# v001.net
KiCad netlist of a schematic drawn in EAGLE
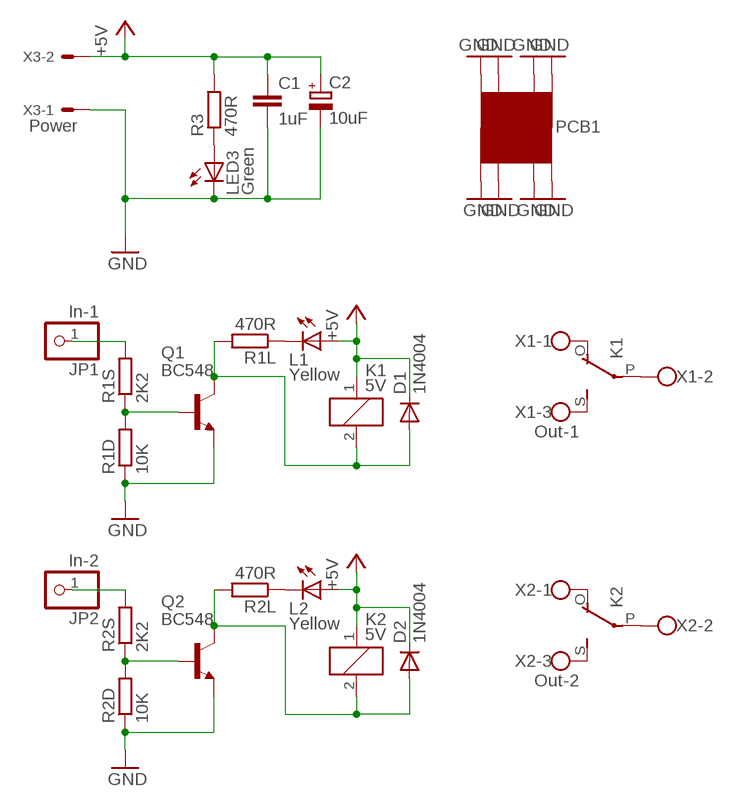
[diagram p0: schematic, sheet 1]

(export (version "E")
  (design (tool "Eeschema 10.0.6"))
  (components
    (comp (ref "C1")
      (value "1uF")
      (footprint "eagle-import:C050-035X075")
      (libsource (lib "eagle-import") (part "C-EU050-035X075"))
    )
    (comp (ref "C2")
      (value "10uF")
      (footprint "eagle-import:E2,5-5")
      (libsource (lib "eagle-import") (part "CPOL-EUE2.5-5"))
    )
    (comp (ref "D1")
      (value "1N4004")
      (footprint "eagle-import:DO41-10")
      (libsource (lib "eagle-import") (part "1N4004"))
    )
    (comp (ref "D2")
      (value "1N4004")
      (footprint "eagle-import:DO41-10")
      (libsource (lib "eagle-import") (part "1N4004"))
    )
    (comp (ref "JP1")
      (value "In-1")
      (footprint "eagle-import:1X01")
      (libsource (lib "eagle-import") (part "PINHD-1X1"))
    )
    (comp (ref "JP2")
      (value "In-2")
      (footprint "eagle-import:1X01")
      (libsource (lib "eagle-import") (part "PINHD-1X1"))
    )
    (comp (ref "K1")
      (value "5V")
      (footprint "eagle-import:G5LE")
      (libsource (lib "eagle-import") (part "G5L"))
    )
    (comp (ref "K2")
      (value "5V")
      (footprint "eagle-import:G5LE")
      (libsource (lib "eagle-import") (part "G5L"))
    )
    (comp (ref "L1")
      (value "Yellow")
      (footprint "eagle-import:LED3MM")
      (libsource (lib "eagle-import") (part "LED3MM"))
    )
    (comp (ref "L2")
      (value "Yellow")
      (footprint "eagle-import:LED3MM")
      (libsource (lib "eagle-import") (part "LED3MM"))
    )
    (comp (ref "LED3")
      (value "Green")
      (footprint "eagle-import:LED3MM")
      (libsource (lib "eagle-import") (part "LED3MM"))
    )
    (comp (ref "PCB1")
      (value "PCB05X05")
      (footprint "eagle-import:PCB_05X05")
      (libsource (lib "eagle-import") (part "PCB05X05"))
    )
    (comp (ref "Q1")
      (value "BC548")
      (footprint "eagle-import:TO92-EBC")
      (libsource (lib "eagle-import") (part "BC548"))
    )
    (comp (ref "Q2")
      (value "BC548")
      (footprint "eagle-import:TO92-EBC")
      (libsource (lib "eagle-import") (part "BC548"))
    )
    (comp (ref "R1D")
      (value "10K")
      (footprint "eagle-import:0204_7")
      (libsource (lib "eagle-import") (part "R-EU_0204/7"))
    )
    (comp (ref "R1L")
      (value "470R")
      (footprint "eagle-import:0204_7")
      (libsource (lib "eagle-import") (part "R-EU_0204/7"))
    )
    (comp (ref "R1S")
      (value "2K2")
      (footprint "eagle-import:0204_7")
      (libsource (lib "eagle-import") (part "R-EU_0204/7"))
    )
    (comp (ref "R2D")
      (value "10K")
      (footprint "eagle-import:0204_7")
      (libsource (lib "eagle-import") (part "R-EU_0204/7"))
    )
    (comp (ref "R2L")
      (value "470R")
      (footprint "eagle-import:0204_7")
      (libsource (lib "eagle-import") (part "R-EU_0204/7"))
    )
    (comp (ref "R2S")
      (value "2K2")
      (footprint "eagle-import:0204_7")
      (libsource (lib "eagle-import") (part "R-EU_0204/7"))
    )
    (comp (ref "R3")
      (value "470R")
      (footprint "eagle-import:0207_2V")
      (libsource (lib "eagle-import") (part "resistor_R-EU_0207/2V"))
    )
    (comp (ref "X1")
      (value "Out-1")
      (footprint "eagle-import:W237-103")
      (fields (field (name "MPN") "237-103"))
      (libsource (lib "eagle-import") (part "W237-103"))
    )
    (comp (ref "X2")
      (value "Out-2")
      (footprint "eagle-import:W237-103")
      (fields (field (name "MPN") "237-103"))
      (libsource (lib "eagle-import") (part "W237-103"))
    )
    (comp (ref "X3")
      (value "Power")
      (footprint "eagle-import:6410-02")
      (libsource (lib "eagle-import") (part "22-?-0227-2021"))
    )
  )
  (nets
    (net (code "1") (name "+5V") (class "Default")
      (node (ref "C1") (pin "1") (pinfunction "1_1") (pintype "passive"))
      (node (ref "C2") (pin "+") (pinfunction "+_+") (pintype "passive"))
      (node (ref "D1") (pin "C") (pinfunction "C_C") (pintype "passive"))
      (node (ref "D2") (pin "C") (pinfunction "C_C") (pintype "passive"))
      (node (ref "K1") (pin "1") (pinfunction "1_1") (pintype "passive"))
      (node (ref "K2") (pin "1") (pinfunction "1_1") (pintype "passive"))
      (node (ref "L1") (pin "A") (pinfunction "A_A") (pintype "passive"))
      (node (ref "L2") (pin "A") (pinfunction "A_A") (pintype "passive"))
      (node (ref "R3") (pin "2") (pinfunction "2_2") (pintype "passive"))
      (node (ref "X3") (pin "2") (pinfunction "S_2") (pintype "passive"))
    )
    (net (code "2") (name "GND") (class "Default")
      (node (ref "C1") (pin "2") (pinfunction "2_2") (pintype "passive"))
      (node (ref "C2") (pin "-") (pinfunction "-_-") (pintype "passive"))
      (node (ref "LED3") (pin "K") (pinfunction "C_K") (pintype "passive"))
      (node (ref "PCB1") (pin "GND@1") (pinfunction "GND_GND@1") (pintype "bidirectional"))
      (node (ref "PCB1") (pin "GND@2") (pinfunction "GND_GND@2") (pintype "bidirectional"))
      (node (ref "PCB1") (pin "GND@3") (pinfunction "GND_GND@3") (pintype "bidirectional"))
      (node (ref "PCB1") (pin "GND@4") (pinfunction "GND_GND@4") (pintype "bidirectional"))
      (node (ref "PCB1") (pin "GND@5") (pinfunction "GND_GND@5") (pintype "bidirectional"))
      (node (ref "PCB1") (pin "GND@6") (pinfunction "GND_GND@6") (pintype "bidirectional"))
      (node (ref "PCB1") (pin "GND@7") (pinfunction "GND_GND@7") (pintype "bidirectional"))
      (node (ref "PCB1") (pin "GND@8") (pinfunction "GND_GND@8") (pintype "bidirectional"))
      (node (ref "Q1") (pin "E") (pinfunction "E_E") (pintype "passive"))
      (node (ref "Q2") (pin "E") (pinfunction "E_E") (pintype "passive"))
      (node (ref "R1D") (pin "1") (pinfunction "1_1") (pintype "passive"))
      (node (ref "R2D") (pin "1") (pinfunction "1_1") (pintype "passive"))
      (node (ref "X3") (pin "1") (pinfunction "S_1") (pintype "passive"))
    )
    (net (code "3") (name "Net-(D1-PadA)") (class "Default")
      (node (ref "D1") (pin "A") (pinfunction "A_A") (pintype "passive"))
      (node (ref "K1") (pin "2") (pinfunction "2_2") (pintype "passive"))
      (node (ref "Q1") (pin "C") (pinfunction "C_C") (pintype "passive"))
      (node (ref "R1L") (pin "2") (pinfunction "2_2") (pintype "passive"))
    )
    (net (code "4") (name "Net-(D2-PadA)") (class "Default")
      (node (ref "D2") (pin "A") (pinfunction "A_A") (pintype "passive"))
      (node (ref "K2") (pin "2") (pinfunction "2_2") (pintype "passive"))
      (node (ref "Q2") (pin "C") (pinfunction "C_C") (pintype "passive"))
      (node (ref "R2L") (pin "2") (pinfunction "2_2") (pintype "passive"))
    )
    (net (code "5") (name "Net-(JP1-Pad1)") (class "Default")
      (node (ref "JP1") (pin "1") (pinfunction "1_1") (pintype "passive"))
      (node (ref "R1S") (pin "2") (pinfunction "2_2") (pintype "passive"))
    )
    (net (code "6") (name "Net-(JP2-Pad1)") (class "Default")
      (node (ref "JP2") (pin "1") (pinfunction "1_1") (pintype "passive"))
      (node (ref "R2S") (pin "2") (pinfunction "2_2") (pintype "passive"))
    )
    (net (code "7") (name "Net-(L1-C)") (class "Default")
      (node (ref "L1") (pin "K") (pinfunction "C_K") (pintype "passive"))
      (node (ref "R1L") (pin "1") (pinfunction "1_1") (pintype "passive"))
    )
    (net (code "8") (name "Net-(L2-C)") (class "Default")
      (node (ref "L2") (pin "K") (pinfunction "C_K") (pintype "passive"))
      (node (ref "R2L") (pin "1") (pinfunction "1_1") (pintype "passive"))
    )
    (net (code "9") (name "Net-(LED3-PadA)") (class "Default")
      (node (ref "LED3") (pin "A") (pinfunction "A_A") (pintype "passive"))
      (node (ref "R3") (pin "1") (pinfunction "1_1") (pintype "passive"))
    )
    (net (code "10") (name "Net-(Q1-PadB)") (class "Default")
      (node (ref "Q1") (pin "B") (pinfunction "B_B") (pintype "passive"))
      (node (ref "R1D") (pin "2") (pinfunction "2_2") (pintype "passive"))
      (node (ref "R1S") (pin "1") (pinfunction "1_1") (pintype "passive"))
    )
    (net (code "11") (name "Net-(Q2-PadB)") (class "Default")
      (node (ref "Q2") (pin "B") (pinfunction "B_B") (pintype "passive"))
      (node (ref "R2D") (pin "2") (pinfunction "2_2") (pintype "passive"))
      (node (ref "R2S") (pin "1") (pinfunction "1_1") (pintype "passive"))
    )
    (net (code "12") (name "Net-(X1A-KL)") (class "Default")
      (node (ref "K1") (pin "O") (pinfunction "O_O") (pintype "passive"))
      (node (ref "X1") (pin "1") (pinfunction "KL_1") (pintype "passive"))
    )
    (net (code "13") (name "Net-(X1B-KL)") (class "Default")
      (node (ref "K1") (pin "P") (pinfunction "P_P") (pintype "passive"))
      (node (ref "X1") (pin "2") (pinfunction "KL_2") (pintype "passive"))
    )
    (net (code "14") (name "Net-(X1C-KL)") (class "Default")
      (node (ref "K1") (pin "S") (pinfunction "S_S") (pintype "passive"))
      (node (ref "X1") (pin "3") (pinfunction "KL_3") (pintype "passive"))
    )
    (net (code "15") (name "Net-(X2A-KL)") (class "Default")
      (node (ref "K2") (pin "O") (pinfunction "O_O") (pintype "passive"))
      (node (ref "X2") (pin "1") (pinfunction "KL_1") (pintype "passive"))
    )
    (net (code "16") (name "Net-(X2B-KL)") (class "Default")
      (node (ref "K2") (pin "P") (pinfunction "P_P") (pintype "passive"))
      (node (ref "X2") (pin "2") (pinfunction "KL_2") (pintype "passive"))
    )
    (net (code "17") (name "Net-(X2C-KL)") (class "Default")
      (node (ref "K2") (pin "S") (pinfunction "S_S") (pintype "passive"))
      (node (ref "X2") (pin "3") (pinfunction "KL_3") (pintype "passive"))
    )
  )
)
